# Supply.net
KiCad netlist of a schematic drawn in Altium Designer
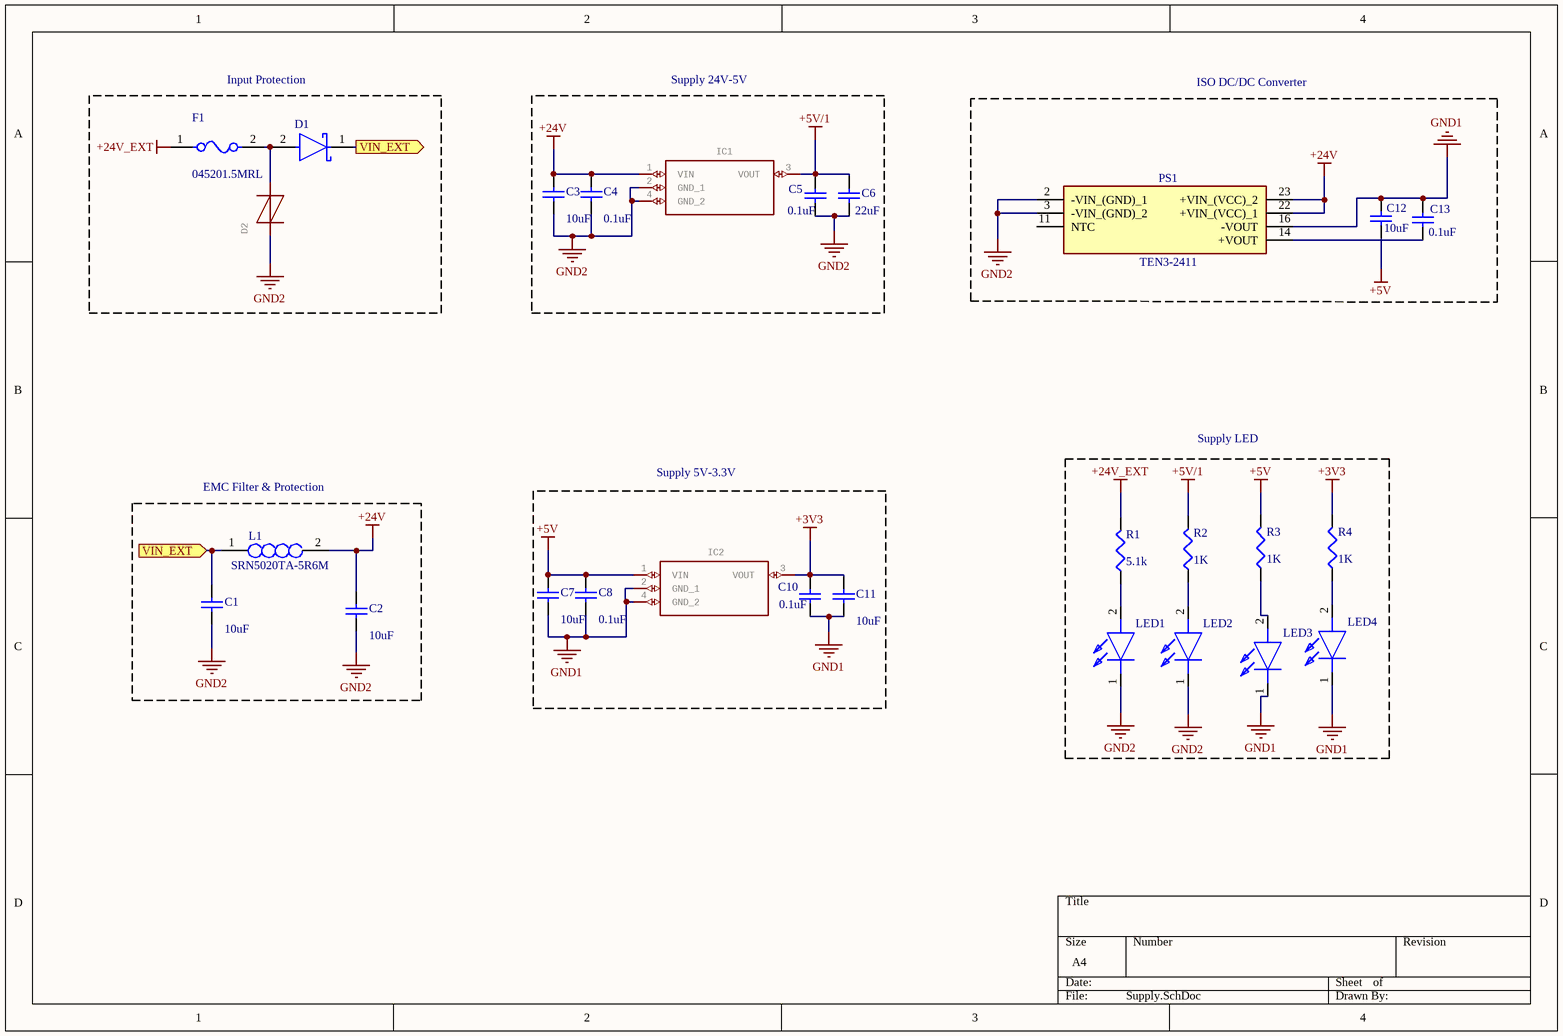
[diagram p0: Supply.SchDoc]

(export (version "E")
  (design (tool "Eeschema 10.0.6"))
  (components
    (comp (ref "C1")
      (value "10uF")
      (footprint "1608[0603]")
      (description "Capacitor (Semiconductor SIM Model)")
      (fields (field (name "Comment") "Cap Semi") (field (name "PUBLISHER") "Altium Limited"))
      (libsource (lib "Miscellaneous Devices") (part "Cap Semi"))
    )
    (comp (ref "C2")
      (value "10uF")
      (footprint "1608[0603]")
      (description "Capacitor (Semiconductor SIM Model)")
      (fields (field (name "Comment") "Cap Semi") (field (name "PUBLISHER") "Altium Limited"))
      (libsource (lib "Miscellaneous Devices") (part "Cap Semi"))
    )
    (comp (ref "C3")
      (value "10uF")
      (footprint "1608[0603]")
      (description "Capacitor (Semiconductor SIM Model)")
      (fields (field (name "Comment") "Cap Semi") (field (name "PUBLISHER") "Altium Limited"))
      (libsource (lib "Miscellaneous Devices") (part "Cap Semi"))
    )
    (comp (ref "C4")
      (value "0.1uF")
      (footprint "1608[0603]")
      (description "Capacitor (Semiconductor SIM Model)")
      (fields (field (name "Comment") "Cap Semi") (field (name "PUBLISHER") "Altium Limited"))
      (libsource (lib "Miscellaneous Devices") (part "Cap Semi"))
    )
    (comp (ref "C5")
      (value "0.1uF")
      (footprint "1608[0603]")
      (description "Capacitor (Semiconductor SIM Model)")
      (fields (field (name "Comment") "Cap Semi") (field (name "PUBLISHER") "Altium Limited"))
      (libsource (lib "Miscellaneous Devices") (part "Cap Semi"))
    )
    (comp (ref "C6")
      (value "22uF")
      (footprint "1608[0603]")
      (description "Capacitor (Semiconductor SIM Model)")
      (fields (field (name "Comment") "Cap Semi") (field (name "PUBLISHER") "Altium Limited"))
      (libsource (lib "Miscellaneous Devices") (part "Cap Semi"))
    )
    (comp (ref "C7")
      (value "10uF")
      (footprint "1608[0603]")
      (description "Capacitor (Semiconductor SIM Model)")
      (fields (field (name "Comment") "Cap Semi") (field (name "PUBLISHER") "Altium Limited"))
      (libsource (lib "Miscellaneous Devices") (part "Cap Semi"))
    )
    (comp (ref "C8")
      (value "0.1uF")
      (footprint "1608[0603]")
      (description "Capacitor (Semiconductor SIM Model)")
      (fields (field (name "Comment") "Cap Semi") (field (name "PUBLISHER") "Altium Limited"))
      (libsource (lib "Miscellaneous Devices") (part "Cap Semi"))
    )
    (comp (ref "C10")
      (value "0.1uF")
      (footprint "1608[0603]")
      (description "Capacitor (Semiconductor SIM Model)")
      (fields (field (name "Comment") "Cap Semi") (field (name "PUBLISHER") "Altium Limited"))
      (libsource (lib "Miscellaneous Devices") (part "Cap Semi"))
    )
    (comp (ref "C11")
      (value "10uF")
      (footprint "1608[0603]")
      (description "Capacitor (Semiconductor SIM Model)")
      (fields (field (name "Comment") "Cap Semi") (field (name "PUBLISHER") "Altium Limited"))
      (libsource (lib "Miscellaneous Devices") (part "Cap Semi"))
    )
    (comp (ref "C12")
      (value "10uF")
      (footprint "C1206")
      (description "Capacitor (Semiconductor SIM Model)")
      (fields (field (name "Comment") "Cap Semi") (field (name "PUBLISHER") "Altium Limited"))
      (libsource (lib "Miscellaneous Devices") (part "Cap Semi"))
    )
    (comp (ref "C13")
      (value "0.1uF")
      (footprint "C1206")
      (description "Capacitor (Semiconductor SIM Model)")
      (fields (field (name "Comment") "Cap Semi") (field (name "PUBLISHER") "Altium Limited"))
      (libsource (lib "Miscellaneous Devices") (part "Cap Semi"))
    )
    (comp (ref "D1")
      (value "NRVTSS5100ET3G")
      (footprint "FP-403A-03-MFG")
      (description "Trench Schottky Rectifier, Very Low Leakage, 100V, 5A,")
      (fields
        (field (name "MANUFACTURER") "ON Semiconductor")
        (field (name "OCTOPART") "https://octopart.com/nrvtss5100et3g-on+semiconductor-54318003")
      )
      (libsource (lib "Altium Content Vault") (part "1d6ec82d83fb6aee721767c19dac4b9"))
    )
    (comp (ref "D2")
      (value "Thyristor Surge Protection Devices (TSPD) 500A 25V")
      (footprint "LIBRARY_DIODES_FUSE_SMB")
      (fields (field (name "LIBRARYNAME") "COMPAQ"))
      (libsource (lib "COMPAC (1)") (part "P0300SCLRP"))
    )
    (comp (ref "F1")
      (value "045201.5MRL")
      (footprint "FP-0452-MFG")
      (description "FUSE BRD MNT 1.5A 125VAC/VDC SMD")
      (fields
        (field (name "MANUFACTURER") "Littelfuse Inc")
        (field (name "OCTOPART") "https://octopart.com/045201.5mrl-littelfuse-566412")
      )
      (libsource (lib "Altium Content Vault") (part "5bcf9b9f640e542cf0359d10258e979"))
    )
    (comp (ref "IC1")
      (value "LDO LDO Voltage Regulators 5.0V/400MA LDO + Tab-Pin SOT-223")
      (footprint "SOT223")
      (fields (field (name "LIBRARYNAME") "COMPAQ"))
      (libsource (lib "COMPAC (1)") (part "NCV4274CST50T3G"))
    )
    (comp (ref "IC2")
      (value "LDO Regulator 3.3V 1% 300mA SOT223 ON Semiconductor MC33275ST-3.3T3G, LDO Voltage Regulator, 300mA, 3.3 V, Maximum of 13 Vin, 3 + Tab-Pin SOT-223   Source:  Datasheet")
      (footprint "SOT223")
      (fields (field (name "LIBRARYNAME") "COMPAQ"))
      (libsource (lib "COMPAC (1)") (part "MC33275ST-3.3T3G"))
    )
    (comp (ref "L1")
      (value "SRN5020TA-5R6M")
      (footprint "SamacSys:INDPM5050X200N")
      (description "Inductor")
      (fields (field (name "MOUSER PART NUMBER") "652-SRN5020TA-5R6M"))
      (libsource (lib "SamacSys") (part "SRN5020TA-5R6M"))
    )
    (comp (ref "LED1")
      (value "SML-D12D1WT86")
      (footprint "SamacSys:LEDC1608X55N")
      (description "LED")
      (fields (field (name "MOUSER PART NUMBER") "755-SML-D12D1WT86"))
      (libsource (lib "SamacSys") (part "SML-D12D1WT86"))
    )
    (comp (ref "LED2")
      (value "SML-D12D1WT86")
      (footprint "SamacSys:LEDC1608X55N")
      (description "LED")
      (fields (field (name "MOUSER PART NUMBER") "755-SML-D12D1WT86"))
      (libsource (lib "SamacSys") (part "SML-D12D1WT86"))
    )
    (comp (ref "LED3")
      (value "SML-D12D1WT86")
      (footprint "SamacSys:LEDC1608X55N")
      (description "LED")
      (fields (field (name "MOUSER PART NUMBER") "755-SML-D12D1WT86"))
      (libsource (lib "SamacSys") (part "SML-D12D1WT86"))
    )
    (comp (ref "LED4")
      (value "SML-D12D1WT86")
      (footprint "SamacSys:LEDC1608X55N")
      (description "LED")
      (fields (field (name "MOUSER PART NUMBER") "755-SML-D12D1WT86"))
      (libsource (lib "SamacSys") (part "SML-D12D1WT86"))
    )
    (comp (ref "PS1")
      (value "TEN3-2411")
      (footprint "SamacSys:TEN30515N")
      (description "Power Supply")
      (libsource (lib "SamacSys") (part "TEN3-2411"))
    )
    (comp (ref "R1")
      (value "5.1k")
      (footprint "J1-0603")
      (description "Resistor")
      (fields (field (name "Comment") "Res3") (field (name "PUBLISHER") "Altium Limited"))
      (libsource (lib "Miscellaneous Devices") (part "Res3"))
    )
    (comp (ref "R2")
      (value "1K")
      (footprint "J1-0603")
      (description "Resistor")
      (fields (field (name "Comment") "Res3") (field (name "PUBLISHER") "Altium Limited"))
      (libsource (lib "Miscellaneous Devices") (part "Res3"))
    )
    (comp (ref "R3")
      (value "1K")
      (footprint "J1-0603")
      (description "Resistor")
      (fields (field (name "Comment") "Res3") (field (name "PUBLISHER") "Altium Limited"))
      (libsource (lib "Miscellaneous Devices") (part "Res3"))
    )
    (comp (ref "R4")
      (value "1K")
      (footprint "J1-0603")
      (description "Resistor")
      (fields (field (name "Comment") "Res3") (field (name "PUBLISHER") "Altium Limited"))
      (libsource (lib "Miscellaneous Devices") (part "Res3"))
    )
  )
  (nets
    (net (code "1") (name "+3V3") (class "Default")
      (node (ref "C10") (pin "2") (pinfunction "2_2") (pintype "passive"))
      (node (ref "C11") (pin "2") (pinfunction "2_2") (pintype "passive"))
      (node (ref "IC2") (pin "3") (pinfunction "VOUT_3") (pintype "bidirectional"))
      (node (ref "R4") (pin "2") (pinfunction "2_2") (pintype "passive"))
    )
    (net (code "2") (name "+5V") (class "Default")
      (node (ref "C12") (pin "1") (pinfunction "1_1") (pintype "passive"))
      (node (ref "C7") (pin "2") (pinfunction "2_2") (pintype "passive"))
      (node (ref "C8") (pin "2") (pinfunction "2_2") (pintype "passive"))
      (node (ref "IC2") (pin "1") (pinfunction "VIN_1") (pintype "bidirectional"))
      (node (ref "R3") (pin "2") (pinfunction "2_2") (pintype "passive"))
    )
    (net (code "3") (name "+5V{slash}1") (class "Default")
      (node (ref "C5") (pin "2") (pinfunction "2_2") (pintype "passive"))
      (node (ref "C6") (pin "2") (pinfunction "2_2") (pintype "passive"))
      (node (ref "IC1") (pin "3") (pinfunction "VOUT_3") (pintype "bidirectional"))
      (node (ref "R2") (pin "2") (pinfunction "2_2") (pintype "passive"))
    )
    (net (code "4") (name "+24V") (class "Default")
      (node (ref "C2") (pin "2") (pinfunction "2_2") (pintype "passive"))
      (node (ref "C3") (pin "2") (pinfunction "2_2") (pintype "passive"))
      (node (ref "C4") (pin "2") (pinfunction "2_2") (pintype "passive"))
      (node (ref "IC1") (pin "1") (pinfunction "VIN_1") (pintype "bidirectional"))
      (node (ref "L1") (pin "2") (pinfunction "2_2") (pintype "passive"))
      (node (ref "PS1") (pin "22") (pinfunction "+VIN_(VCC)_1_22") (pintype "passive"))
      (node (ref "PS1") (pin "23") (pinfunction "+VIN_(VCC)_2_23") (pintype "passive"))
    )
    (net (code "5") (name "+24V_EXT") (class "Default")
      (node (ref "F1") (pin "1") (pinfunction "1_1") (pintype "passive"))
      (node (ref "R1") (pin "2") (pinfunction "2_2") (pintype "passive"))
    )
    (net (code "6") (name "/VIN_EXT") (class "Default")
      (node (ref "C1") (pin "2") (pinfunction "2_2") (pintype "passive"))
      (node (ref "D1") (pin "1") (pinfunction "C_1") (pintype "passive"))
      (node (ref "L1") (pin "1") (pinfunction "1_1") (pintype "passive"))
    )
    (net (code "7") (name "GND1") (class "Default")
      (node (ref "C10") (pin "1") (pinfunction "1_1") (pintype "passive"))
      (node (ref "C11") (pin "1") (pinfunction "1_1") (pintype "passive"))
      (node (ref "C12") (pin "2") (pinfunction "2_2") (pintype "passive"))
      (node (ref "C13") (pin "2") (pinfunction "2_2") (pintype "passive"))
      (node (ref "C7") (pin "1") (pinfunction "1_1") (pintype "passive"))
      (node (ref "C8") (pin "1") (pinfunction "1_1") (pintype "passive"))
      (node (ref "IC2") (pin "2") (pinfunction "GND_1_2") (pintype "bidirectional"))
      (node (ref "IC2") (pin "4") (pinfunction "GND_2_4") (pintype "bidirectional"))
      (node (ref "LED3") (pin "1") (pinfunction "K_1") (pintype "passive"))
      (node (ref "LED4") (pin "1") (pinfunction "K_1") (pintype "passive"))
      (node (ref "PS1") (pin "16") (pinfunction "-VOUT_16") (pintype "passive"))
    )
    (net (code "8") (name "GND2") (class "Default")
      (node (ref "C1") (pin "1") (pinfunction "1_1") (pintype "passive"))
      (node (ref "C2") (pin "1") (pinfunction "1_1") (pintype "passive"))
      (node (ref "C3") (pin "1") (pinfunction "1_1") (pintype "passive"))
      (node (ref "C4") (pin "1") (pinfunction "1_1") (pintype "passive"))
      (node (ref "C5") (pin "1") (pinfunction "1_1") (pintype "passive"))
      (node (ref "C6") (pin "1") (pinfunction "1_1") (pintype "passive"))
      (node (ref "D2") (pin "2") (pinfunction "T_2") (pintype "passive"))
      (node (ref "IC1") (pin "2") (pinfunction "GND_1_2") (pintype "bidirectional"))
      (node (ref "IC1") (pin "4") (pinfunction "GND_2_4") (pintype "bidirectional"))
      (node (ref "LED1") (pin "1") (pinfunction "K_1") (pintype "passive"))
      (node (ref "LED2") (pin "1") (pinfunction "K_1") (pintype "passive"))
      (node (ref "PS1") (pin "2") (pinfunction "-VIN_(GND)_1_2") (pintype "passive"))
      (node (ref "PS1") (pin "3") (pinfunction "-VIN_(GND)_2_3") (pintype "passive"))
    )
    (net (code "9") (name "Net-(D1-A)") (class "Default")
      (node (ref "D1") (pin "2") (pinfunction "A_2") (pintype "passive"))
      (node (ref "D2") (pin "1") (pinfunction "R_1") (pintype "passive"))
      (node (ref "F1") (pin "2") (pinfunction "2_2") (pintype "passive"))
    )
    (net (code "10") (name "Net-(LED1-A)") (class "Default")
      (node (ref "LED1") (pin "2") (pinfunction "A_2") (pintype "passive"))
      (node (ref "R1") (pin "1") (pinfunction "1_1") (pintype "passive"))
    )
    (net (code "11") (name "Net-(LED2-A)") (class "Default")
      (node (ref "LED2") (pin "2") (pinfunction "A_2") (pintype "passive"))
      (node (ref "R2") (pin "1") (pinfunction "1_1") (pintype "passive"))
    )
    (net (code "12") (name "Net-(LED3-A)") (class "Default")
      (node (ref "LED3") (pin "2") (pinfunction "A_2") (pintype "passive"))
      (node (ref "R3") (pin "1") (pinfunction "1_1") (pintype "passive"))
    )
    (net (code "13") (name "Net-(LED4-A)") (class "Default")
      (node (ref "LED4") (pin "2") (pinfunction "A_2") (pintype "passive"))
      (node (ref "R4") (pin "1") (pinfunction "1_1") (pintype "passive"))
    )
    (net (code "14") (name "Net-(PS1-+VOUT)") (class "Default")
      (node (ref "C13") (pin "1") (pinfunction "1_1") (pintype "passive"))
      (node (ref "PS1") (pin "14") (pinfunction "+VOUT_14") (pintype "passive"))
    )
    (net (code "15") (name "unconnected-(PS1-NTC-Pad11)") (class "Default")
      (node (ref "PS1") (pin "11") (pinfunction "NTC_11") (pintype "passive"))
    )
  )
)
